# main_3.net
KiCad netlist of a schematic drawn in Altium Designer
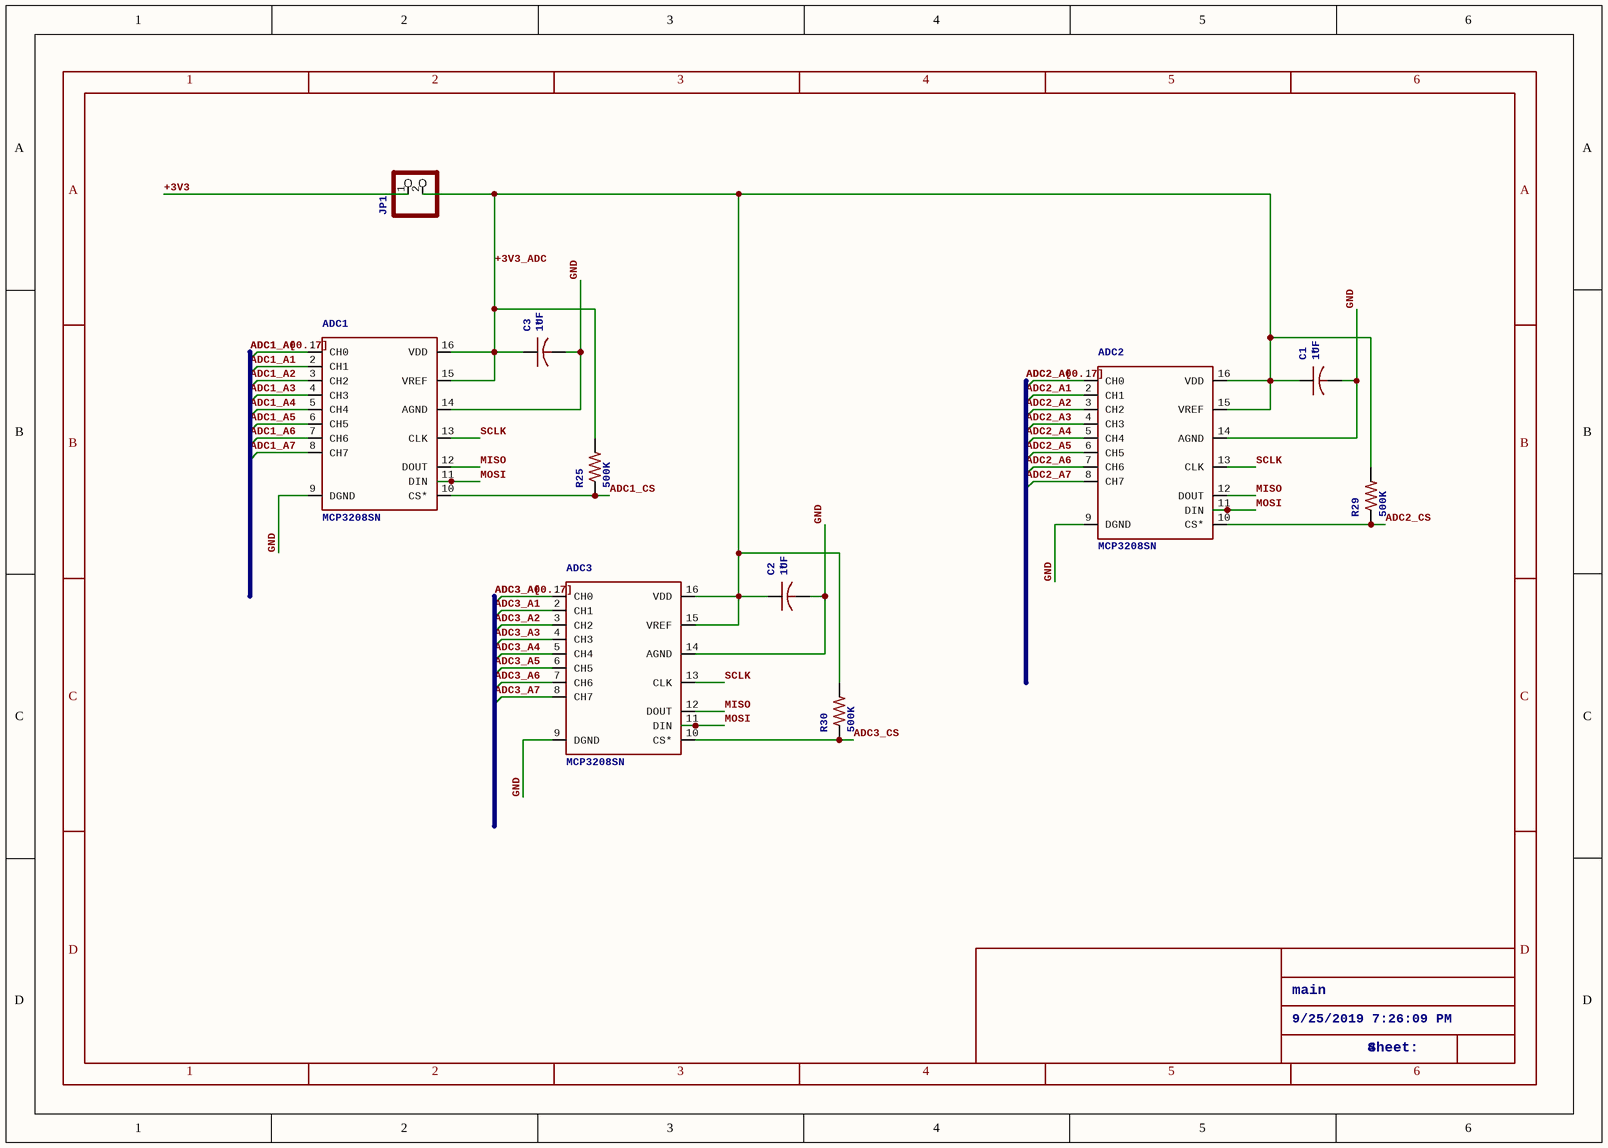
[diagram p0: main_3.SchDoc]

(export (version "E")
  (design (tool "Eeschema 10.0.6"))
  (components
    (comp (ref "ADC1")
      (value "MCP3208SN")
      (footprint "SO-16")
      (fields
        (field (name "MF") "MICROCHIP")
        (field (name "MPN") "MCP3202-CI/SN")
        (field (name "LIBRARYNAME") "microchip-extra")
      )
      (libsource (lib "microchip-extra") (part "MCP3208SN"))
    )
    (comp (ref "ADC2")
      (value "MCP3208SN")
      (footprint "SO-16")
      (fields
        (field (name "MF") "MICROCHIP")
        (field (name "MPN") "MCP3202-CI/SN")
        (field (name "LIBRARYNAME") "microchip-extra")
      )
      (libsource (lib "microchip-extra") (part "MCP3208SN"))
    )
    (comp (ref "ADC3")
      (value "MCP3208SN")
      (footprint "SO-16")
      (fields
        (field (name "MF") "MICROCHIP")
        (field (name "MPN") "MCP3202-CI/SN")
        (field (name "LIBRARYNAME") "microchip-extra")
      )
      (libsource (lib "microchip-extra") (part "MCP3208SN"))
    )
    (comp (ref "C1")
      (value "1UF")
      (footprint "C0805")
      (description "CAPACITOR, American symbol")
      (fields (field (name "NAME") "*"))
      (libsource (lib "rcl") (part "C-USC0805"))
    )
    (comp (ref "C2")
      (value "1UF")
      (footprint "C0805")
      (description "CAPACITOR, American symbol")
      (fields (field (name "NAME") "*"))
      (libsource (lib "rcl") (part "C-USC0805"))
    )
    (comp (ref "C3")
      (value "1UF")
      (footprint "C0805")
      (description "CAPACITOR, American symbol")
      (fields (field (name "NAME") "*"))
      (libsource (lib "rcl") (part "C-USC0805"))
    )
    (comp (ref "JP1")
      (value "PINHD-1X2")
      (footprint "1X02")
      (description "PIN HEADER")
      (fields (field (name "LIBRARYNAME") "pinhead"))
      (libsource (lib "pinhead") (part "PINHD-1X2"))
    )
    (comp (ref "R25")
      (value "500K")
      (footprint "R0805")
      (description "RESISTOR, American symbol")
      (libsource (lib "rcl") (part "R-US_R0805"))
    )
    (comp (ref "R29")
      (value "500K")
      (footprint "R0805")
      (description "RESISTOR, American symbol")
      (libsource (lib "rcl") (part "R-US_R0805"))
    )
    (comp (ref "R30")
      (value "500K")
      (footprint "R0805")
      (description "RESISTOR, American symbol")
      (libsource (lib "rcl") (part "R-US_R0805"))
    )
  )
  (nets
    (net (code "25") (name "/+3V3") (class "Default")
      (node (ref "JP1") (pin "1") (pinfunction "1_1") (pintype "passive"))
    )
    (net (code "26") (name "/+3V3_ADC") (class "Default")
      (node (ref "ADC1") (pin "15") (pinfunction "VREF_15") (pintype "passive"))
      (node (ref "ADC1") (pin "16") (pinfunction "VDD_16") (pintype "passive"))
      (node (ref "ADC2") (pin "15") (pinfunction "VREF_15") (pintype "passive"))
      (node (ref "ADC2") (pin "16") (pinfunction "VDD_16") (pintype "passive"))
      (node (ref "ADC3") (pin "15") (pinfunction "VREF_15") (pintype "passive"))
      (node (ref "ADC3") (pin "16") (pinfunction "VDD_16") (pintype "passive"))
      (node (ref "C1") (pin "1") (pinfunction "1_1") (pintype "passive"))
      (node (ref "C2") (pin "1") (pinfunction "1_1") (pintype "passive"))
      (node (ref "C3") (pin "1") (pinfunction "1_1") (pintype "passive"))
      (node (ref "JP1") (pin "2") (pinfunction "2_2") (pintype "passive"))
      (node (ref "R25") (pin "2") (pinfunction "2_2") (pintype "passive"))
      (node (ref "R29") (pin "2") (pinfunction "2_2") (pintype "passive"))
      (node (ref "R30") (pin "2") (pinfunction "2_2") (pintype "passive"))
    )
    (net (code "28") (name "/ADC1_CS") (class "Default")
      (node (ref "ADC1") (pin "10") (pinfunction "CS*_10") (pintype "passive"))
      (node (ref "R25") (pin "1") (pinfunction "1_1") (pintype "passive"))
    )
    (net (code "30") (name "/ADC2_CS") (class "Default")
      (node (ref "ADC2") (pin "10") (pinfunction "CS*_10") (pintype "passive"))
      (node (ref "R29") (pin "1") (pinfunction "1_1") (pintype "passive"))
    )
    (net (code "32") (name "/ADC3_CS") (class "Default")
      (node (ref "ADC3") (pin "10") (pinfunction "CS*_10") (pintype "passive"))
      (node (ref "R30") (pin "1") (pinfunction "1_1") (pintype "passive"))
    )
    (net (code "33") (name "/GND") (class "Default")
      (node (ref "ADC1") (pin "14") (pinfunction "AGND_14") (pintype "passive"))
      (node (ref "ADC1") (pin "9") (pinfunction "DGND_9") (pintype "passive"))
      (node (ref "ADC2") (pin "14") (pinfunction "AGND_14") (pintype "passive"))
      (node (ref "ADC2") (pin "9") (pinfunction "DGND_9") (pintype "passive"))
      (node (ref "ADC3") (pin "14") (pinfunction "AGND_14") (pintype "passive"))
      (node (ref "ADC3") (pin "9") (pinfunction "DGND_9") (pintype "passive"))
      (node (ref "C1") (pin "2") (pinfunction "2_2") (pintype "passive"))
      (node (ref "C2") (pin "2") (pinfunction "2_2") (pintype "passive"))
      (node (ref "C3") (pin "2") (pinfunction "2_2") (pintype "passive"))
    )
    (net (code "34") (name "/MISO") (class "Default")
      (node (ref "ADC1") (pin "12") (pinfunction "DOUT_12") (pintype "passive"))
      (node (ref "ADC2") (pin "12") (pinfunction "DOUT_12") (pintype "passive"))
      (node (ref "ADC3") (pin "12") (pinfunction "DOUT_12") (pintype "passive"))
    )
    (net (code "35") (name "/MOSI") (class "Default")
      (node (ref "ADC1") (pin "11") (pinfunction "DIN_11") (pintype "passive"))
      (node (ref "ADC2") (pin "11") (pinfunction "DIN_11") (pintype "passive"))
      (node (ref "ADC3") (pin "11") (pinfunction "DIN_11") (pintype "passive"))
    )
    (net (code "36") (name "/SCLK") (class "Default")
      (node (ref "ADC1") (pin "13") (pinfunction "CLK_13") (pintype "passive"))
      (node (ref "ADC2") (pin "13") (pinfunction "CLK_13") (pintype "passive"))
      (node (ref "ADC3") (pin "13") (pinfunction "CLK_13") (pintype "passive"))
    )
    (net (code "37") (name "unconnected-(ADC1-CH0-Pad1)") (class "Default")
      (node (ref "ADC1") (pin "1") (pinfunction "CH0_1") (pintype "passive"))
    )
    (net (code "38") (name "unconnected-(ADC1-CH1-Pad2)") (class "Default")
      (node (ref "ADC1") (pin "2") (pinfunction "CH1_2") (pintype "passive"))
    )
    (net (code "39") (name "unconnected-(ADC1-CH2-Pad3)") (class "Default")
      (node (ref "ADC1") (pin "3") (pinfunction "CH2_3") (pintype "passive"))
    )
    (net (code "40") (name "unconnected-(ADC1-CH3-Pad4)") (class "Default")
      (node (ref "ADC1") (pin "4") (pinfunction "CH3_4") (pintype "passive"))
    )
    (net (code "41") (name "unconnected-(ADC1-CH4-Pad5)") (class "Default")
      (node (ref "ADC1") (pin "5") (pinfunction "CH4_5") (pintype "passive"))
    )
    (net (code "42") (name "unconnected-(ADC1-CH5-Pad6)") (class "Default")
      (node (ref "ADC1") (pin "6") (pinfunction "CH5_6") (pintype "passive"))
    )
    (net (code "43") (name "unconnected-(ADC1-CH6-Pad7)") (class "Default")
      (node (ref "ADC1") (pin "7") (pinfunction "CH6_7") (pintype "passive"))
    )
    (net (code "44") (name "unconnected-(ADC1-CH7-Pad8)") (class "Default")
      (node (ref "ADC1") (pin "8") (pinfunction "CH7_8") (pintype "passive"))
    )
    (net (code "45") (name "unconnected-(ADC2-CH0-Pad1)") (class "Default")
      (node (ref "ADC2") (pin "1") (pinfunction "CH0_1") (pintype "passive"))
    )
    (net (code "46") (name "unconnected-(ADC2-CH1-Pad2)") (class "Default")
      (node (ref "ADC2") (pin "2") (pinfunction "CH1_2") (pintype "passive"))
    )
    (net (code "47") (name "unconnected-(ADC2-CH2-Pad3)") (class "Default")
      (node (ref "ADC2") (pin "3") (pinfunction "CH2_3") (pintype "passive"))
    )
    (net (code "48") (name "unconnected-(ADC2-CH3-Pad4)") (class "Default")
      (node (ref "ADC2") (pin "4") (pinfunction "CH3_4") (pintype "passive"))
    )
    (net (code "49") (name "unconnected-(ADC2-CH4-Pad5)") (class "Default")
      (node (ref "ADC2") (pin "5") (pinfunction "CH4_5") (pintype "passive"))
    )
    (net (code "50") (name "unconnected-(ADC2-CH5-Pad6)") (class "Default")
      (node (ref "ADC2") (pin "6") (pinfunction "CH5_6") (pintype "passive"))
    )
    (net (code "51") (name "unconnected-(ADC2-CH6-Pad7)") (class "Default")
      (node (ref "ADC2") (pin "7") (pinfunction "CH6_7") (pintype "passive"))
    )
    (net (code "52") (name "unconnected-(ADC2-CH7-Pad8)") (class "Default")
      (node (ref "ADC2") (pin "8") (pinfunction "CH7_8") (pintype "passive"))
    )
    (net (code "53") (name "unconnected-(ADC3-CH0-Pad1)") (class "Default")
      (node (ref "ADC3") (pin "1") (pinfunction "CH0_1") (pintype "passive"))
    )
    (net (code "54") (name "unconnected-(ADC3-CH1-Pad2)") (class "Default")
      (node (ref "ADC3") (pin "2") (pinfunction "CH1_2") (pintype "passive"))
    )
    (net (code "55") (name "unconnected-(ADC3-CH2-Pad3)") (class "Default")
      (node (ref "ADC3") (pin "3") (pinfunction "CH2_3") (pintype "passive"))
    )
    (net (code "56") (name "unconnected-(ADC3-CH3-Pad4)") (class "Default")
      (node (ref "ADC3") (pin "4") (pinfunction "CH3_4") (pintype "passive"))
    )
    (net (code "57") (name "unconnected-(ADC3-CH4-Pad5)") (class "Default")
      (node (ref "ADC3") (pin "5") (pinfunction "CH4_5") (pintype "passive"))
    )
    (net (code "58") (name "unconnected-(ADC3-CH5-Pad6)") (class "Default")
      (node (ref "ADC3") (pin "6") (pinfunction "CH5_6") (pintype "passive"))
    )
    (net (code "59") (name "unconnected-(ADC3-CH6-Pad7)") (class "Default")
      (node (ref "ADC3") (pin "7") (pinfunction "CH6_7") (pintype "passive"))
    )
    (net (code "60") (name "unconnected-(ADC3-CH7-Pad8)") (class "Default")
      (node (ref "ADC3") (pin "8") (pinfunction "CH7_8") (pintype "passive"))
    )
  )
)
